# schematic.net
KiCad netlist of a schematic drawn in Altium Designer
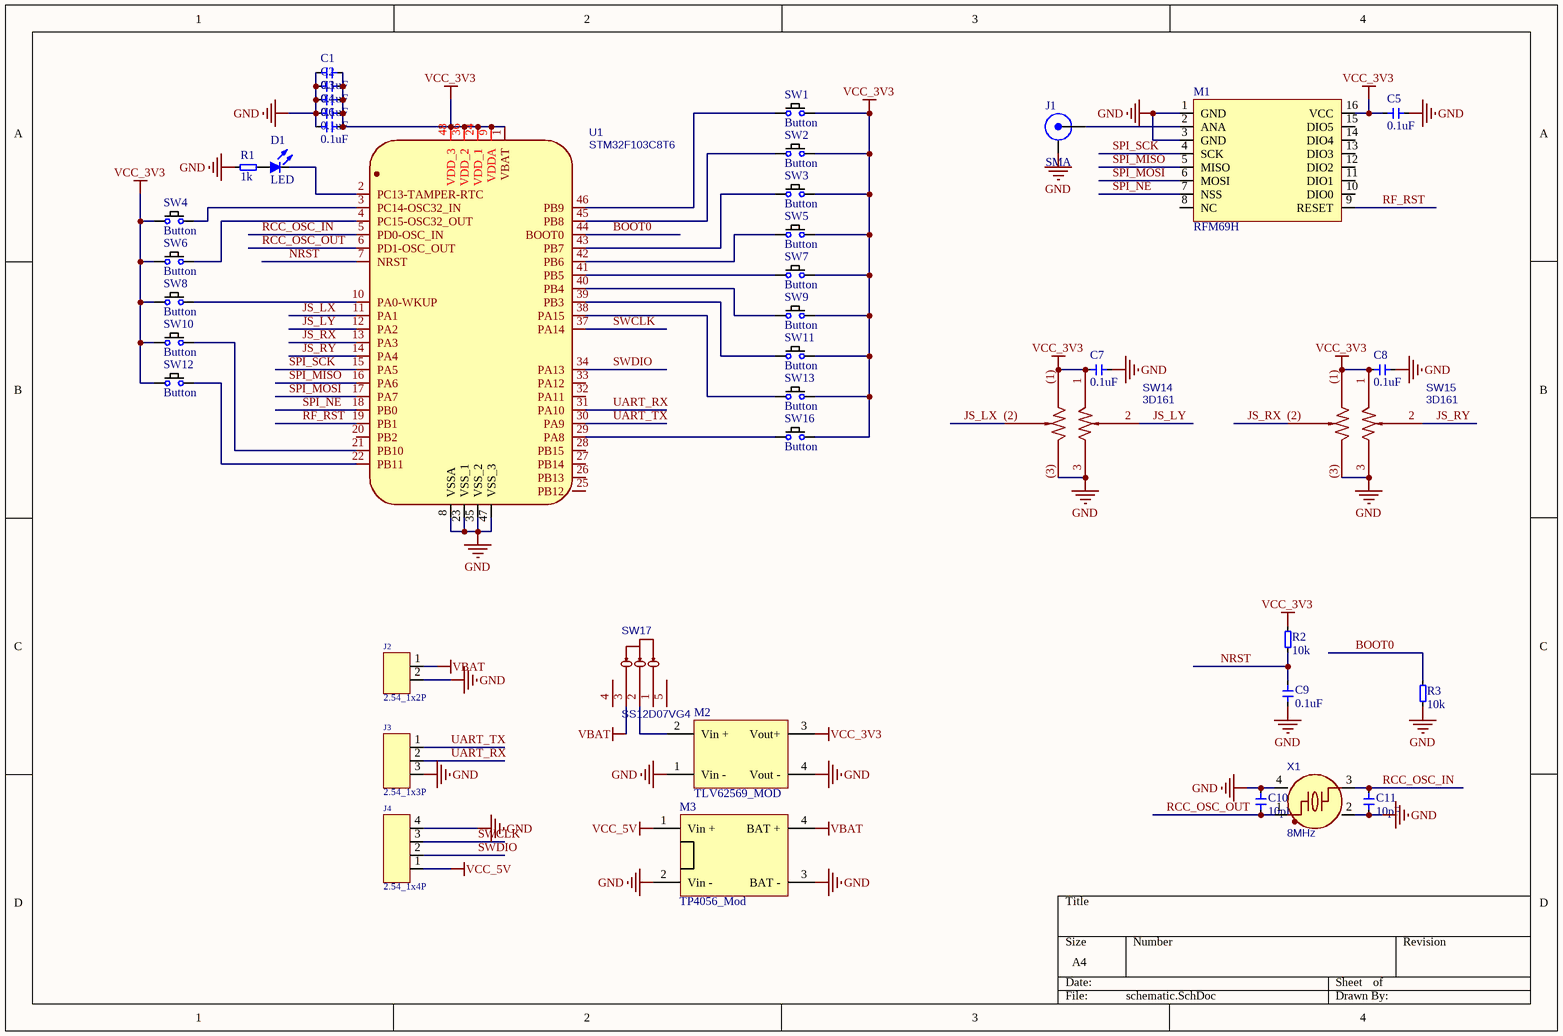
[diagram p0: schematic.SchDoc]

(export (version "E")
  (design (tool "Eeschema 10.0.6"))
  (components
    (comp (ref "C1") (value "0.1uF") (footprint "0402") (libsource (lib "pants1") (part "Cap")))
    (comp (ref "C2") (value "0.1uF") (footprint "0402") (libsource (lib "pants1") (part "Cap")))
    (comp (ref "C3") (value "0.1uF") (footprint "0402") (libsource (lib "pants1") (part "Cap")))
    (comp (ref "C4") (value "0.1uF") (footprint "0402") (libsource (lib "pants1") (part "Cap")))
    (comp (ref "C5") (value "0.1uF") (footprint "0402") (libsource (lib "pants1") (part "Cap")))
    (comp (ref "C6") (value "0.1uF") (footprint "0402") (libsource (lib "pants1") (part "Cap")))
    (comp (ref "C7") (value "0.1uF") (footprint "0402") (libsource (lib "pants1") (part "Cap")))
    (comp (ref "C8") (value "0.1uF") (footprint "0402") (libsource (lib "pants1") (part "Cap")))
    (comp (ref "C9") (value "0.1uF") (footprint "0402") (libsource (lib "pants1") (part "Cap")))
    (comp (ref "C10") (value "10pF") (footprint "0402") (libsource (lib "pants1") (part "Cap")))
    (comp (ref "C11") (value "10pF") (footprint "0402") (libsource (lib "pants1") (part "Cap")))
    (comp (ref "D1") (value "LED") (footprint "0603LED") (libsource (lib "pants1") (part "LED")))
    (comp (ref "J1") (value "SMA") (footprint "SMA_Edge") (libsource (lib "pants1") (part "Coax")))
    (comp (ref "J2")
      (value "2.54_1x2P")
      (footprint "2.54排针_1x2立式")
      (libsource (lib "2.54排针") (part "2.54_1x2P"))
    )
    (comp (ref "J3")
      (value "2.54_1x3P")
      (footprint "2.54排针_1x3立式")
      (libsource (lib "2.54排针") (part "2.54_1x3P"))
    )
    (comp (ref "J4")
      (value "2.54_1x4P")
      (footprint "2.54排针_1x4立式")
      (libsource (lib "2.54排针") (part "2.54_1x4P"))
    )
    (comp (ref "M1") (value "RFM69H") (footprint "RFM69H") (libsource (lib "pants1") (part "RFM69H")))
    (comp (ref "M2") (value "TLV62569_MOD") (footprint "DM13") (libsource (lib "pants1") (part "DM13")))
    (comp (ref "M3")
      (value "TP4056_Mod")
      (footprint "TP4056_Mod_1")
      (libsource (lib "pants1") (part "TP4056_Mod"))
    )
    (comp (ref "R1")
      (value "1k")
      (footprint "0402")
      (description "Resistor")
      (libsource (lib "") (part "Res_1"))
    )
    (comp (ref "R2")
      (value "10k")
      (footprint "0402")
      (description "Resistor")
      (libsource (lib "pants1") (part "Res"))
    )
    (comp (ref "R3")
      (value "10k")
      (footprint "0402")
      (description "Resistor")
      (libsource (lib "pants1") (part "Res"))
    )
    (comp (ref "SW1")
      (value "Button")
      (footprint "KEY-SMD_4P-L6.0-W6.0-P4.50-LS8.6")
      (libsource (lib "pants1") (part "Button"))
    )
    (comp (ref "SW2")
      (value "Button")
      (footprint "KEY-SMD_4P-L6.0-W6.0-P4.50-LS8.6")
      (libsource (lib "pants1") (part "Button"))
    )
    (comp (ref "SW3")
      (value "Button")
      (footprint "KEY-SMD_4P-L6.0-W6.0-P4.50-LS8.6")
      (libsource (lib "pants1") (part "Button"))
    )
    (comp (ref "SW4")
      (value "Button")
      (footprint "KEY-SMD_4P-L6.0-W6.0-P4.50-LS8.6")
      (libsource (lib "pants1") (part "Button"))
    )
    (comp (ref "SW5")
      (value "Button")
      (footprint "KEY-SMD_4P-L6.0-W6.0-P4.50-LS8.6")
      (libsource (lib "pants1") (part "Button"))
    )
    (comp (ref "SW6")
      (value "Button")
      (footprint "KEY-SMD_4P-L6.0-W6.0-P4.50-LS8.6")
      (libsource (lib "pants1") (part "Button"))
    )
    (comp (ref "SW7")
      (value "Button")
      (footprint "KEY-SMD_4P-L6.0-W6.0-P4.50-LS8.6")
      (libsource (lib "pants1") (part "Button"))
    )
    (comp (ref "SW8")
      (value "Button")
      (footprint "KEY-SMD_4P-L6.0-W6.0-P4.50-LS8.6")
      (libsource (lib "pants1") (part "Button"))
    )
    (comp (ref "SW9")
      (value "Button")
      (footprint "KEY-SMD_4P-L6.0-W6.0-P4.50-LS8.6")
      (libsource (lib "pants1") (part "Button"))
    )
    (comp (ref "SW10")
      (value "Button")
      (footprint "KEY-SMD_4P-L6.0-W6.0-P4.50-LS8.6")
      (libsource (lib "pants1") (part "Button"))
    )
    (comp (ref "SW11")
      (value "Button")
      (footprint "KEY-SMD_4P-L6.0-W6.0-P4.50-LS8.6")
      (libsource (lib "pants1") (part "Button"))
    )
    (comp (ref "SW12")
      (value "Button")
      (footprint "KEY-SMD_4P-L6.0-W6.0-P4.50-LS8.6")
      (libsource (lib "pants1") (part "Button"))
    )
    (comp (ref "SW13")
      (value "Button")
      (footprint "KEY-SMD_4P-L6.0-W6.0-P4.50-LS8.6")
      (libsource (lib "pants1") (part "Button"))
    )
    (comp (ref "SW14")
      (value "3D161")
      (footprint "SW-TH_3D161")
      (fields (field (name "BOM_SUPPLIER PART") "C92593") (field (name "CONTRIBUTOR") "LCSC"))
      (libsource (lib "pants1") (part "3D161"))
    )
    (comp (ref "SW15")
      (value "3D161")
      (footprint "SW-TH_3D161")
      (fields (field (name "BOM_SUPPLIER PART") "C92593") (field (name "CONTRIBUTOR") "LCSC"))
      (libsource (lib "pants1") (part "3D161"))
    )
    (comp (ref "SW16")
      (value "Button")
      (footprint "KEY-SMD_4P-L6.0-W6.0-P4.50-LS8.6")
      (libsource (lib "pants1") (part "Button"))
    )
    (comp (ref "SW17")
      (value "SS12D07VG4")
      (footprint "SW-TH_SS12D07VG4")
      (fields (field (name "BOM_SUPPLIER PART") "C431546") (field (name "CONTRIBUTOR") "LCSC"))
      (libsource (lib "pants1") (part "SS12D07VG4"))
    )
    (comp (ref "U1")
      (value "STM32F103C8T6")
      (footprint "LQFP-48_L7.0-W7.0-P0.50-LS9.0-BL")
      (fields (field (name "BOM_SUPPLIER PART") "C8734"))
      (libsource (lib "pants1") (part "STM32F103C8T6"))
    )
    (comp (ref "X1")
      (value "8MHz")
      (footprint "OSC-SMD_4P-L3.2-W2.5-BL")
      (fields
        (field (name "BOM_SUPPLIER PART") "C518156")
        (field (name "BOM_MANUFACTURER PART") "3225-8.00-20-10-10/A")
        (field (name "CONTRIBUTOR") "LCSC")
      )
      (libsource (lib "pants1") (part "Crystal_4P"))
    )
  )
  (nets
    (net (code "1") (name "/BOOT0") (class "Default")
      (node (ref "R3") (pin "2") (pinfunction "2_2") (pintype "passive"))
      (node (ref "U1") (pin "44") (pinfunction "BOOT0_44") (pintype "passive"))
    )
    (net (code "2") (name "/JS_LX") (class "Default")
      (node (ref "SW14") (pin "(2)") (pinfunction "(2)_(2)") (pintype "passive"))
      (node (ref "U1") (pin "11") (pinfunction "PA1_11") (pintype "passive"))
    )
    (net (code "3") (name "/JS_LY") (class "Default")
      (node (ref "SW14") (pin "2") (pinfunction "2_2") (pintype "passive"))
      (node (ref "U1") (pin "12") (pinfunction "PA2_12") (pintype "passive"))
    )
    (net (code "4") (name "/JS_RX") (class "Default")
      (node (ref "SW15") (pin "(2)") (pinfunction "(2)_(2)") (pintype "passive"))
      (node (ref "U1") (pin "13") (pinfunction "PA3_13") (pintype "passive"))
    )
    (net (code "5") (name "/JS_RY") (class "Default")
      (node (ref "SW15") (pin "2") (pinfunction "2_2") (pintype "passive"))
      (node (ref "U1") (pin "14") (pinfunction "PA4_14") (pintype "passive"))
    )
    (net (code "6") (name "/NRST") (class "Default")
      (node (ref "C9") (pin "2") (pinfunction "2_2") (pintype "passive"))
      (node (ref "R2") (pin "1") (pinfunction "1_1") (pintype "passive"))
      (node (ref "U1") (pin "7") (pinfunction "NRST_7") (pintype "passive"))
    )
    (net (code "7") (name "/RCC_OSC_IN") (class "Default")
      (node (ref "C11") (pin "2") (pinfunction "2_2") (pintype "passive"))
      (node (ref "U1") (pin "5") (pinfunction "PD0-OSC_IN_5") (pintype "passive"))
      (node (ref "X1") (pin "3") (pinfunction "3_3") (pintype "passive"))
    )
    (net (code "8") (name "/RCC_OSC_OUT") (class "Default")
      (node (ref "C10") (pin "1") (pinfunction "1_1") (pintype "passive"))
      (node (ref "U1") (pin "6") (pinfunction "PD1-OSC_OUT_6") (pintype "passive"))
      (node (ref "X1") (pin "1") (pinfunction "1_1") (pintype "passive"))
    )
    (net (code "9") (name "/RF_RST") (class "Default")
      (node (ref "M1") (pin "9") (pinfunction "RESET_9") (pintype "passive"))
      (node (ref "U1") (pin "19") (pinfunction "PB1_19") (pintype "passive"))
    )
    (net (code "10") (name "/SPI_MISO") (class "Default")
      (node (ref "M1") (pin "5") (pinfunction "MISO_5") (pintype "passive"))
      (node (ref "U1") (pin "16") (pinfunction "PA6_16") (pintype "passive"))
    )
    (net (code "11") (name "/SPI_MOSI") (class "Default")
      (node (ref "M1") (pin "6") (pinfunction "MOSI_6") (pintype "passive"))
      (node (ref "U1") (pin "17") (pinfunction "PA7_17") (pintype "passive"))
    )
    (net (code "12") (name "/SPI_NE") (class "Default")
      (node (ref "M1") (pin "7") (pinfunction "NSS_7") (pintype "passive"))
      (node (ref "U1") (pin "18") (pinfunction "PB0_18") (pintype "passive"))
    )
    (net (code "13") (name "/SPI_SCK") (class "Default")
      (node (ref "M1") (pin "4") (pinfunction "SCK_4") (pintype "passive"))
      (node (ref "U1") (pin "15") (pinfunction "PA5_15") (pintype "passive"))
    )
    (net (code "14") (name "/SWCLK") (class "Default")
      (node (ref "J4") (pin "3") (pinfunction "3_3") (pintype "passive"))
      (node (ref "U1") (pin "37") (pinfunction "PA14_37") (pintype "passive"))
    )
    (net (code "15") (name "/SWDIO") (class "Default")
      (node (ref "J4") (pin "2") (pinfunction "2_2") (pintype "passive"))
      (node (ref "U1") (pin "34") (pinfunction "PA13_34") (pintype "passive"))
    )
    (net (code "16") (name "/UART_RX") (class "Default")
      (node (ref "J3") (pin "2") (pinfunction "2_2") (pintype "passive"))
      (node (ref "U1") (pin "31") (pinfunction "PA10_31") (pintype "passive"))
    )
    (net (code "17") (name "/UART_TX") (class "Default")
      (node (ref "J3") (pin "1") (pinfunction "1_1") (pintype "passive"))
      (node (ref "U1") (pin "30") (pinfunction "PA9_30") (pintype "passive"))
    )
    (net (code "18") (name "GND") (class "Default")
      (node (ref "C1") (pin "2") (pinfunction "2_2") (pintype "passive"))
      (node (ref "C10") (pin "2") (pinfunction "2_2") (pintype "passive"))
      (node (ref "C11") (pin "1") (pinfunction "1_1") (pintype "passive"))
      (node (ref "C2") (pin "2") (pinfunction "2_2") (pintype "passive"))
      (node (ref "C3") (pin "2") (pinfunction "2_2") (pintype "passive"))
      (node (ref "C4") (pin "2") (pinfunction "2_2") (pintype "passive"))
      (node (ref "C5") (pin "2") (pinfunction "2_2") (pintype "passive"))
      (node (ref "C6") (pin "2") (pinfunction "2_2") (pintype "passive"))
      (node (ref "C7") (pin "2") (pinfunction "2_2") (pintype "passive"))
      (node (ref "C8") (pin "2") (pinfunction "2_2") (pintype "passive"))
      (node (ref "C9") (pin "1") (pinfunction "1_1") (pintype "passive"))
      (node (ref "J1") (pin "2") (pintype "passive"))
      (node (ref "J2") (pin "2") (pinfunction "2_2") (pintype "passive"))
      (node (ref "J3") (pin "3") (pinfunction "3_3") (pintype "passive"))
      (node (ref "J4") (pin "4") (pinfunction "4_4") (pintype "passive"))
      (node (ref "M1") (pin "1") (pinfunction "GND_1") (pintype "passive"))
      (node (ref "M1") (pin "3") (pinfunction "GND_3") (pintype "passive"))
      (node (ref "M2") (pin "1") (pinfunction "Vin_-_1") (pintype "passive"))
      (node (ref "M2") (pin "4") (pinfunction "Vout_-_4") (pintype "passive"))
      (node (ref "M3") (pin "2") (pinfunction "Vin_-_2") (pintype "passive"))
      (node (ref "M3") (pin "3") (pinfunction "BAT_-_3") (pintype "passive"))
      (node (ref "R1") (pin "1") (pinfunction "1_1") (pintype "passive"))
      (node (ref "R3") (pin "1") (pinfunction "1_1") (pintype "passive"))
      (node (ref "SW14") (pin "(3)") (pinfunction "(3)_(3)") (pintype "passive"))
      (node (ref "SW14") (pin "3") (pinfunction "3_3") (pintype "passive"))
      (node (ref "SW15") (pin "(3)") (pinfunction "(3)_(3)") (pintype "passive"))
      (node (ref "SW15") (pin "3") (pinfunction "3_3") (pintype "passive"))
      (node (ref "U1") (pin "23") (pinfunction "VSS_1_23") (pintype "passive"))
      (node (ref "U1") (pin "35") (pinfunction "VSS_2_35") (pintype "passive"))
      (node (ref "U1") (pin "47") (pinfunction "VSS_3_47") (pintype "passive"))
      (node (ref "U1") (pin "8") (pinfunction "VSSA_8") (pintype "passive"))
      (node (ref "X1") (pin "2") (pinfunction "GND_2") (pintype "passive"))
      (node (ref "X1") (pin "4") (pinfunction "GND_4") (pintype "passive"))
    )
    (net (code "19") (name "Net-(D1-PadA)") (class "Default")
      (node (ref "D1") (pin "A") (pinfunction "A_A") (pintype "passive"))
      (node (ref "R1") (pin "2") (pinfunction "2_2") (pintype "passive"))
    )
    (net (code "20") (name "Net-(M1-ANA)") (class "Default")
      (node (ref "J1") (pin "1") (pintype "passive"))
      (node (ref "M1") (pin "2") (pinfunction "ANA_2") (pintype "passive"))
    )
    (net (code "21") (name "Net-(M2-Vin_+)") (class "Default")
      (node (ref "M2") (pin "2") (pinfunction "Vin_+_2") (pintype "passive"))
      (node (ref "SW17") (pin "2") (pinfunction "2_2") (pintype "passive"))
    )
    (net (code "22") (name "Net-(U1-PA0-WKUP)") (class "Default")
      (node (ref "SW8") (pin "2") (pinfunction "2_2") (pintype "passive"))
      (node (ref "U1") (pin "10") (pinfunction "PA0-WKUP_10") (pintype "passive"))
    )
    (net (code "23") (name "Net-(U1-PA8)") (class "Default")
      (node (ref "SW16") (pin "1") (pinfunction "1_1") (pintype "passive"))
      (node (ref "U1") (pin "29") (pinfunction "PA8_29") (pintype "passive"))
    )
    (net (code "24") (name "Net-(U1-PA15)") (class "Default")
      (node (ref "SW13") (pin "1") (pinfunction "1_1") (pintype "passive"))
      (node (ref "U1") (pin "38") (pinfunction "PA15_38") (pintype "passive"))
    )
    (net (code "25") (name "Net-(U1-PB3)") (class "Default")
      (node (ref "SW11") (pin "1") (pinfunction "1_1") (pintype "passive"))
      (node (ref "U1") (pin "39") (pinfunction "PB3_39") (pintype "passive"))
    )
    (net (code "26") (name "Net-(U1-PB4)") (class "Default")
      (node (ref "SW9") (pin "1") (pinfunction "1_1") (pintype "passive"))
      (node (ref "U1") (pin "40") (pinfunction "PB4_40") (pintype "passive"))
    )
    (net (code "27") (name "Net-(U1-PB5)") (class "Default")
      (node (ref "SW7") (pin "1") (pinfunction "1_1") (pintype "passive"))
      (node (ref "U1") (pin "41") (pinfunction "PB5_41") (pintype "passive"))
    )
    (net (code "28") (name "Net-(U1-PB6)") (class "Default")
      (node (ref "SW5") (pin "1") (pinfunction "1_1") (pintype "passive"))
      (node (ref "U1") (pin "42") (pinfunction "PB6_42") (pintype "passive"))
    )
    (net (code "29") (name "Net-(U1-PB7)") (class "Default")
      (node (ref "SW3") (pin "1") (pinfunction "1_1") (pintype "passive"))
      (node (ref "U1") (pin "43") (pinfunction "PB7_43") (pintype "passive"))
    )
    (net (code "30") (name "Net-(U1-PB8)") (class "Default")
      (node (ref "SW2") (pin "1") (pinfunction "1_1") (pintype "passive"))
      (node (ref "U1") (pin "45") (pinfunction "PB8_45") (pintype "passive"))
    )
    (net (code "31") (name "Net-(U1-PB9)") (class "Default")
      (node (ref "SW1") (pin "1") (pinfunction "1_1") (pintype "passive"))
      (node (ref "U1") (pin "46") (pinfunction "PB9_46") (pintype "passive"))
    )
    (net (code "32") (name "Net-(U1-PB10)") (class "Default")
      (node (ref "SW10") (pin "2") (pinfunction "2_2") (pintype "passive"))
      (node (ref "U1") (pin "21") (pinfunction "PB10_21") (pintype "passive"))
    )
    (net (code "33") (name "Net-(U1-PB11)") (class "Default")
      (node (ref "SW12") (pin "2") (pinfunction "2_2") (pintype "passive"))
      (node (ref "U1") (pin "22") (pinfunction "PB11_22") (pintype "passive"))
    )
    (net (code "34") (name "Net-(U1-PC13-TAMPER-RTC)") (class "Default")
      (node (ref "D1") (pin "K") (pinfunction "K_K") (pintype "passive"))
      (node (ref "U1") (pin "2") (pinfunction "PC13-TAMPER-RTC_2") (pintype "passive"))
    )
    (net (code "35") (name "Net-(U1-PC14-OSC32_IN)") (class "Default")
      (node (ref "SW4") (pin "2") (pinfunction "2_2") (pintype "passive"))
      (node (ref "U1") (pin "3") (pinfunction "PC14-OSC32_IN_3") (pintype "passive"))
    )
    (net (code "36") (name "Net-(U1-PC15-OSC32_OUT)") (class "Default")
      (node (ref "SW6") (pin "2") (pinfunction "2_2") (pintype "passive"))
      (node (ref "U1") (pin "4") (pinfunction "PC15-OSC32_OUT_4") (pintype "passive"))
    )
    (net (code "37") (name "VBAT") (class "Default")
      (node (ref "J2") (pin "1") (pinfunction "1_1") (pintype "passive"))
      (node (ref "M3") (pin "4") (pinfunction "BAT_+_4") (pintype "passive"))
      (node (ref "SW17") (pin "3") (pinfunction "3_3") (pintype "passive"))
    )
    (net (code "38") (name "VCC_3V3") (class "Default")
      (node (ref "C1") (pin "1") (pinfunction "1_1") (pintype "passive"))
      (node (ref "C2") (pin "1") (pinfunction "1_1") (pintype "passive"))
      (node (ref "C3") (pin "1") (pinfunction "1_1") (pintype "passive"))
      (node (ref "C4") (pin "1") (pinfunction "1_1") (pintype "passive"))
      (node (ref "C5") (pin "1") (pinfunction "1_1") (pintype "passive"))
      (node (ref "C6") (pin "1") (pinfunction "1_1") (pintype "passive"))
      (node (ref "C7") (pin "1") (pinfunction "1_1") (pintype "passive"))
      (node (ref "C8") (pin "1") (pinfunction "1_1") (pintype "passive"))
      (node (ref "M1") (pin "16") (pinfunction "VCC_16") (pintype "passive"))
      (node (ref "M2") (pin "3") (pinfunction "Vout+_3") (pintype "passive"))
      (node (ref "R2") (pin "2") (pinfunction "2_2") (pintype "passive"))
      (node (ref "SW1") (pin "2") (pinfunction "2_2") (pintype "passive"))
      (node (ref "SW10") (pin "1") (pinfunction "1_1") (pintype "passive"))
      (node (ref "SW11") (pin "2") (pinfunction "2_2") (pintype "passive"))
      (node (ref "SW12") (pin "1") (pinfunction "1_1") (pintype "passive"))
      (node (ref "SW13") (pin "2") (pinfunction "2_2") (pintype "passive"))
      (node (ref "SW14") (pin "(1)") (pinfunction "(1)_(1)") (pintype "passive"))
      (node (ref "SW14") (pin "1") (pinfunction "1_1") (pintype "passive"))
      (node (ref "SW15") (pin "(1)") (pinfunction "(1)_(1)") (pintype "passive"))
      (node (ref "SW15") (pin "1") (pinfunction "1_1") (pintype "passive"))
      (node (ref "SW16") (pin "2") (pinfunction "2_2") (pintype "passive"))
      (node (ref "SW2") (pin "2") (pinfunction "2_2") (pintype "passive"))
      (node (ref "SW3") (pin "2") (pinfunction "2_2") (pintype "passive"))
      (node (ref "SW4") (pin "1") (pinfunction "1_1") (pintype "passive"))
      (node (ref "SW5") (pin "2") (pinfunction "2_2") (pintype "passive"))
      (node (ref "SW6") (pin "1") (pinfunction "1_1") (pintype "passive"))
      (node (ref "SW7") (pin "2") (pinfunction "2_2") (pintype "passive"))
      (node (ref "SW8") (pin "1") (pinfunction "1_1") (pintype "passive"))
      (node (ref "SW9") (pin "2") (pinfunction "2_2") (pintype "passive"))
      (node (ref "U1") (pin "1") (pinfunction "VBAT_1") (pintype "passive"))
      (node (ref "U1") (pin "24") (pinfunction "VDD_1_24") (pintype "passive"))
      (node (ref "U1") (pin "36") (pinfunction "VDD_2_36") (pintype "passive"))
      (node (ref "U1") (pin "48") (pinfunction "VDD_3_48") (pintype "passive"))
      (node (ref "U1") (pin "9") (pinfunction "VDDA_9") (pintype "passive"))
    )
    (net (code "39") (name "VCC_5V") (class "Default")
      (node (ref "J4") (pin "1") (pinfunction "1_1") (pintype "passive"))
      (node (ref "M3") (pin "1") (pinfunction "Vin_+_1") (pintype "passive"))
    )
    (net (code "40") (name "unconnected-(M1-DIO0-Pad10)") (class "Default")
      (node (ref "M1") (pin "10") (pinfunction "DIO0_10") (pintype "passive"))
    )
    (net (code "41") (name "unconnected-(M1-DIO1-Pad11)") (class "Default")
      (node (ref "M1") (pin "11") (pinfunction "DIO1_11") (pintype "passive"))
    )
    (net (code "42") (name "unconnected-(M1-DIO2-Pad12)") (class "Default")
      (node (ref "M1") (pin "12") (pinfunction "DIO2_12") (pintype "passive"))
    )
    (net (code "43") (name "unconnected-(M1-DIO3-Pad13)") (class "Default")
      (node (ref "M1") (pin "13") (pinfunction "DIO3_13") (pintype "passive"))
    )
    (net (code "44") (name "unconnected-(M1-DIO4-Pad14)") (class "Default")
      (node (ref "M1") (pin "14") (pinfunction "DIO4_14") (pintype "passive"))
    )
    (net (code "45") (name "unconnected-(M1-DIO5-Pad15)") (class "Default")
      (node (ref "M1") (pin "15") (pinfunction "DIO5_15") (pintype "passive"))
    )
    (net (code "46") (name "unconnected-(M1-NC-Pad8)") (class "Default")
      (node (ref "M1") (pin "8") (pinfunction "NC_8") (pintype "passive"))
    )
    (net (code "47") (name "unconnected-(SW17-Pad1)") (class "Default")
      (node (ref "SW17") (pin "1") (pinfunction "1_1") (pintype "passive"))
    )
    (net (code "48") (name "unconnected-(SW17-Pad4)") (class "Default")
      (node (ref "SW17") (pin "4") (pinfunction "4_4") (pintype "passive"))
    )
    (net (code "49") (name "unconnected-(SW17-Pad5)") (class "Default")
      (node (ref "SW17") (pin "5") (pinfunction "5_5") (pintype "passive"))
    )
    (net (code "50") (name "unconnected-(U1-PA11-Pad32)") (class "Default")
      (node (ref "U1") (pin "32") (pinfunction "PA11_32") (pintype "passive"))
    )
    (net (code "51") (name "unconnected-(U1-PA12-Pad33)") (class "Default")
      (node (ref "U1") (pin "33") (pinfunction "PA12_33") (pintype "passive"))
    )
    (net (code "52") (name "unconnected-(U1-PB2-Pad20)") (class "Default")
      (node (ref "U1") (pin "20") (pinfunction "PB2_20") (pintype "passive"))
    )
    (net (code "53") (name "unconnected-(U1-PB12-Pad25)") (class "Default")
      (node (ref "U1") (pin "25") (pinfunction "PB12_25") (pintype "passive"))
    )
    (net (code "54") (name "unconnected-(U1-PB13-Pad26)") (class "Default")
      (node (ref "U1") (pin "26") (pinfunction "PB13_26") (pintype "passive"))
    )
    (net (code "55") (name "unconnected-(U1-PB14-Pad27)") (class "Default")
      (node (ref "U1") (pin "27") (pinfunction "PB14_27") (pintype "passive"))
    )
    (net (code "56") (name "unconnected-(U1-PB15-Pad28)") (class "Default")
      (node (ref "U1") (pin "28") (pinfunction "PB15_28") (pintype "passive"))
    )
  )
)
